# relayBoard.net
KiCad netlist of a schematic drawn in EAGLE
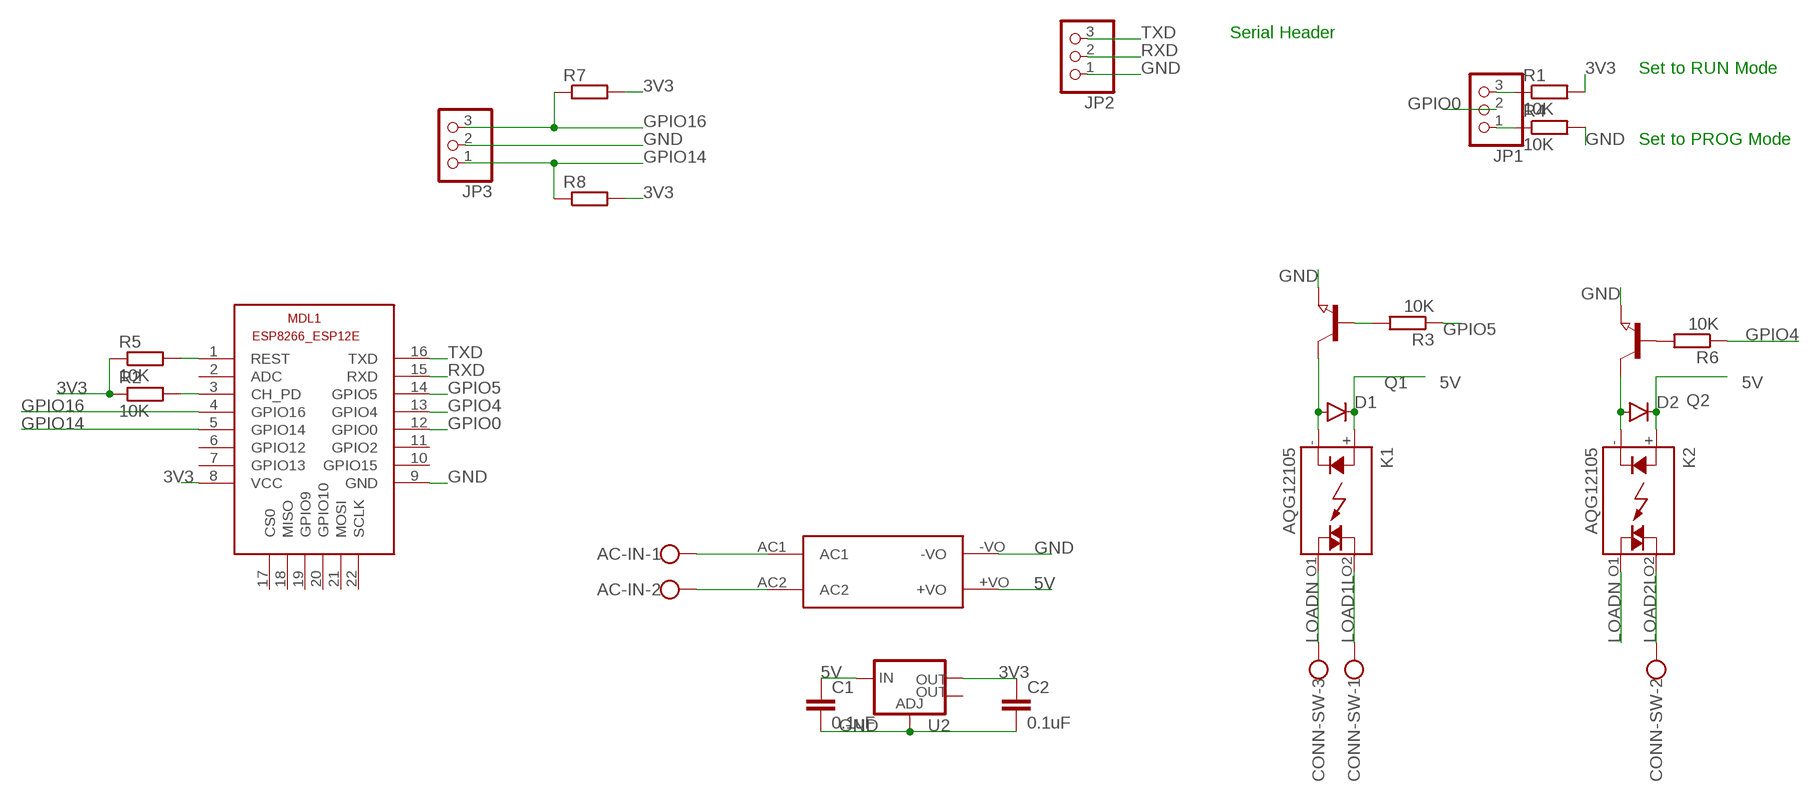
[diagram p0: schematic, sheet 1]

(export (version "E")
  (design (tool "Eeschema 10.0.6"))
  (components
    (comp (ref "AC-IN")
      (value "W237-102")
      (footprint "eagle-import:W237-102")
      (fields (field (name "MPN") "237-102"))
      (libsource (lib "eagle-import") (part "W237-102"))
    )
    (comp (ref "C1")
      (value "0.1uF")
      (footprint "eagle-import:0603-CAP")
      (libsource (lib "eagle-import") (part "0.1UF-25V-5%(0603)"))
    )
    (comp (ref "C2")
      (value "0.1uF")
      (footprint "eagle-import:0603-CAP")
      (libsource (lib "eagle-import") (part "0.1UF-25V-5%(0603)"))
    )
    (comp (ref "CONN-SW")
      (value "W237-103")
      (footprint "eagle-import:W237-103")
      (fields (field (name "MPN") "237-103"))
      (libsource (lib "eagle-import") (part "W237-103"))
    )
    (comp (ref "D1")
      (value "DIODESMA")
      (footprint "eagle-import:SMA-DIODE")
      (libsource (lib "eagle-import") (part "DIODESMA"))
    )
    (comp (ref "D2")
      (value "DIODESMA")
      (footprint "eagle-import:SMA-DIODE")
      (libsource (lib "eagle-import") (part "DIODESMA"))
    )
    (comp (ref "JP1")
      (value "PINHD-1X3")
      (footprint "eagle-import:1X03")
      (libsource (lib "eagle-import") (part "PINHD-1X3"))
    )
    (comp (ref "JP2")
      (value "PINHD-1X3")
      (footprint "eagle-import:1X03")
      (libsource (lib "eagle-import") (part "PINHD-1X3"))
    )
    (comp (ref "JP3")
      (value "PINHD-1X3")
      (footprint "eagle-import:1X03")
      (libsource (lib "eagle-import") (part "PINHD-1X3"))
    )
    (comp (ref "K1")
      (value "AQG12105")
      (footprint "eagle-import:AQG")
      (fields (field (name "MF") "AROMAT/ MATSUSHITA"))
      (libsource (lib "eagle-import") (part "AQG12105"))
    )
    (comp (ref "K2")
      (value "AQG12105")
      (footprint "eagle-import:AQG")
      (fields (field (name "MF") "AROMAT/ MATSUSHITA"))
      (libsource (lib "eagle-import") (part "AQG12105"))
    )
    (comp (ref "MDL1")
      (value "ESP8266-12EESP8266-ESP12E")
      (footprint "eagle-import:ESP8266-ESP12E")
      (libsource (lib "eagle-import") (part "ESP8266-12EESP8266-ESP12E"))
    )
    (comp (ref "Q1")
      (value "NPN-TRANSISTOR_SOT23")
      (footprint "eagle-import:SOT23")
      (libsource (lib "eagle-import") (part "NPN-TRANSISTOR_SOT23"))
    )
    (comp (ref "Q2")
      (value "NPN-TRANSISTOR_SOT23")
      (footprint "eagle-import:SOT23")
      (libsource (lib "eagle-import") (part "NPN-TRANSISTOR_SOT23"))
    )
    (comp (ref "R1")
      (value "10K")
      (footprint "eagle-import:R0805")
      (libsource (lib "eagle-import") (part "R-EU_R0805"))
    )
    (comp (ref "R2")
      (value "10K")
      (footprint "eagle-import:R0805")
      (libsource (lib "eagle-import") (part "R-EU_R0805"))
    )
    (comp (ref "R3")
      (value "10K")
      (footprint "eagle-import:R0805")
      (libsource (lib "eagle-import") (part "R-EU_R0805"))
    )
    (comp (ref "R4")
      (value "10K")
      (footprint "eagle-import:R0805")
      (libsource (lib "eagle-import") (part "R-EU_R0805"))
    )
    (comp (ref "R5")
      (value "10K")
      (footprint "eagle-import:R0805")
      (libsource (lib "eagle-import") (part "R-EU_R0805"))
    )
    (comp (ref "R6")
      (value "10K")
      (footprint "eagle-import:R0805")
      (libsource (lib "eagle-import") (part "R-EU_R0805"))
    )
    (comp (ref "R7")
      (value "R-EU_R0805")
      (footprint "eagle-import:R0805")
      (libsource (lib "eagle-import") (part "R-EU_R0805"))
    )
    (comp (ref "R8")
      (value "R-EU_R0805")
      (footprint "eagle-import:R0805")
      (libsource (lib "eagle-import") (part "R-EU_R0805"))
    )
    (comp (ref "U$4")
      (value "HLK-PM01")
      (footprint "eagle-import:HLK-PM01")
      (libsource (lib "eagle-import") (part "HLK-PM01"))
    )
    (comp (ref "U2")
      (value "V_REG_LM1117SOT223")
      (footprint "eagle-import:SOT223")
      (libsource (lib "eagle-import") (part "V_REG_LM1117SOT223"))
    )
  )
  (nets
    (net (code "1") (name "/3V3") (class "Default")
      (node (ref "C2") (pin "1") (pinfunction "1_1") (pintype "passive"))
      (node (ref "MDL1") (pin "8") (pinfunction "VCC_8") (pintype "bidirectional"))
      (node (ref "R1") (pin "2") (pinfunction "2_2") (pintype "passive"))
      (node (ref "R2") (pin "1") (pinfunction "1_1") (pintype "passive"))
      (node (ref "R5") (pin "1") (pinfunction "1_1") (pintype "passive"))
      (node (ref "R7") (pin "2") (pinfunction "2_2") (pintype "passive"))
      (node (ref "R8") (pin "2") (pinfunction "2_2") (pintype "passive"))
      (node (ref "U2") (pin "2") (pinfunction "OUT_2") (pintype "output"))
    )
    (net (code "2") (name "/5V") (class "Default")
      (node (ref "C1") (pin "1") (pinfunction "1_1") (pintype "passive"))
      (node (ref "D1") (pin "C") (pinfunction "C_C") (pintype "passive"))
      (node (ref "D2") (pin "C") (pinfunction "C_C") (pintype "passive"))
      (node (ref "K1") (pin "+") (pinfunction "A_+") (pintype "passive"))
      (node (ref "K2") (pin "+") (pinfunction "A_+") (pintype "passive"))
      (node (ref "U$4") (pin "+VO") (pinfunction "+VO_+VO") (pintype "bidirectional"))
      (node (ref "U2") (pin "3") (pinfunction "IN_3") (pintype "input"))
    )
    (net (code "3") (name "/GND") (class "Default")
      (node (ref "C1") (pin "2") (pinfunction "2_2") (pintype "passive"))
      (node (ref "C2") (pin "2") (pinfunction "2_2") (pintype "passive"))
      (node (ref "JP2") (pin "1") (pinfunction "1_1") (pintype "passive"))
      (node (ref "JP3") (pin "2") (pinfunction "2_2") (pintype "passive"))
      (node (ref "MDL1") (pin "9") (pinfunction "GND_9") (pintype "bidirectional"))
      (node (ref "Q1") (pin "2") (pinfunction "E_2") (pintype "passive"))
      (node (ref "Q2") (pin "2") (pinfunction "E_2") (pintype "passive"))
      (node (ref "R4") (pin "2") (pinfunction "2_2") (pintype "passive"))
      (node (ref "U$4") (pin "-VO") (pinfunction "-VO_-VO") (pintype "bidirectional"))
      (node (ref "U2") (pin "1") (pinfunction "ADJ_1") (pintype "input"))
    )
    (net (code "4") (name "/GPIO0") (class "Default")
      (node (ref "JP1") (pin "2") (pinfunction "2_2") (pintype "passive"))
      (node (ref "MDL1") (pin "12") (pinfunction "GPIO0_12") (pintype "bidirectional"))
    )
    (net (code "5") (name "/GPIO4") (class "Default")
      (node (ref "MDL1") (pin "13") (pinfunction "GPIO4_13") (pintype "bidirectional"))
      (node (ref "R6") (pin "1") (pinfunction "1_1") (pintype "passive"))
    )
    (net (code "6") (name "/GPIO5") (class "Default")
      (node (ref "MDL1") (pin "14") (pinfunction "GPIO5_14") (pintype "bidirectional"))
      (node (ref "R3") (pin "1") (pinfunction "1_1") (pintype "passive"))
    )
    (net (code "7") (name "/GPIO14") (class "Default")
      (node (ref "JP3") (pin "1") (pinfunction "1_1") (pintype "passive"))
      (node (ref "MDL1") (pin "5") (pinfunction "GPIO14_5") (pintype "bidirectional"))
      (node (ref "R8") (pin "1") (pinfunction "1_1") (pintype "passive"))
    )
    (net (code "8") (name "/GPIO16") (class "Default")
      (node (ref "JP3") (pin "3") (pinfunction "3_3") (pintype "passive"))
      (node (ref "MDL1") (pin "4") (pinfunction "GPIO16_4") (pintype "bidirectional"))
      (node (ref "R7") (pin "1") (pinfunction "1_1") (pintype "passive"))
    )
    (net (code "9") (name "/LOAD1L") (class "Default")
      (node (ref "CONN-SW") (pin "1") (pinfunction "KL_1") (pintype "passive"))
      (node (ref "K1") (pin "O2") (pinfunction "DS1_O2") (pintype "passive"))
    )
    (net (code "10") (name "/LOAD2L") (class "Default")
      (node (ref "CONN-SW") (pin "2") (pinfunction "KL_2") (pintype "passive"))
      (node (ref "K2") (pin "O2") (pinfunction "DS1_O2") (pintype "passive"))
    )
    (net (code "11") (name "/LOADN") (class "Default")
      (node (ref "CONN-SW") (pin "3") (pinfunction "KL_3") (pintype "passive"))
      (node (ref "K1") (pin "O1") (pinfunction "DS2_O1") (pintype "passive"))
      (node (ref "K2") (pin "O1") (pinfunction "DS2_O1") (pintype "passive"))
    )
    (net (code "12") (name "/RXD") (class "Default")
      (node (ref "JP2") (pin "2") (pinfunction "2_2") (pintype "passive"))
      (node (ref "MDL1") (pin "15") (pinfunction "RXD_15") (pintype "bidirectional"))
    )
    (net (code "13") (name "/TXD") (class "Default")
      (node (ref "JP2") (pin "3") (pinfunction "3_3") (pintype "passive"))
      (node (ref "MDL1") (pin "16") (pinfunction "TXD_16") (pintype "bidirectional"))
    )
    (net (code "14") (name "Net-(AC-INA-KL)") (class "Default")
      (node (ref "AC-IN") (pin "1") (pinfunction "KL_1") (pintype "passive"))
      (node (ref "U$4") (pin "AC1") (pinfunction "AC1_AC1") (pintype "bidirectional"))
    )
    (net (code "15") (name "Net-(AC-INB-KL)") (class "Default")
      (node (ref "AC-IN") (pin "2") (pinfunction "KL_2") (pintype "passive"))
      (node (ref "U$4") (pin "AC2") (pinfunction "AC2_AC2") (pintype "bidirectional"))
    )
    (net (code "16") (name "Net-(JP1-Pad1)") (class "Default")
      (node (ref "JP1") (pin "1") (pinfunction "1_1") (pintype "passive"))
      (node (ref "R4") (pin "1") (pinfunction "1_1") (pintype "passive"))
    )
    (net (code "17") (name "Net-(JP1-Pad3)") (class "Default")
      (node (ref "JP1") (pin "3") (pinfunction "3_3") (pintype "passive"))
      (node (ref "R1") (pin "1") (pinfunction "1_1") (pintype "passive"))
    )
    (net (code "18") (name "Net-(K1-K)") (class "Default")
      (node (ref "D1") (pin "A") (pinfunction "A_A") (pintype "passive"))
      (node (ref "K1") (pin "-") (pinfunction "K_-") (pintype "passive"))
      (node (ref "Q1") (pin "3") (pinfunction "C_3") (pintype "passive"))
    )
    (net (code "19") (name "Net-(K2-K)") (class "Default")
      (node (ref "D2") (pin "A") (pinfunction "A_A") (pintype "passive"))
      (node (ref "K2") (pin "-") (pinfunction "K_-") (pintype "passive"))
      (node (ref "Q2") (pin "3") (pinfunction "C_3") (pintype "passive"))
    )
    (net (code "20") (name "Net-(MDL1-CH_PD)") (class "Default")
      (node (ref "MDL1") (pin "3") (pinfunction "CH_PD_3") (pintype "bidirectional"))
      (node (ref "R2") (pin "2") (pinfunction "2_2") (pintype "passive"))
    )
    (net (code "21") (name "Net-(MDL1-REST)") (class "Default")
      (node (ref "MDL1") (pin "1") (pinfunction "REST_1") (pintype "bidirectional"))
      (node (ref "R5") (pin "2") (pinfunction "2_2") (pintype "passive"))
    )
    (net (code "22") (name "Net-(Q1-B)") (class "Default")
      (node (ref "Q1") (pin "1") (pinfunction "B_1") (pintype "passive"))
      (node (ref "R3") (pin "2") (pinfunction "2_2") (pintype "passive"))
    )
    (net (code "23") (name "Net-(Q2-B)") (class "Default")
      (node (ref "Q2") (pin "1") (pinfunction "B_1") (pintype "passive"))
      (node (ref "R6") (pin "2") (pinfunction "2_2") (pintype "passive"))
    )
    (net (code "24") (name "unconnected-(MDL1-ADC-Pad2)") (class "Default")
      (node (ref "MDL1") (pin "2") (pinfunction "ADC_2") (pintype "bidirectional"))
    )
    (net (code "25") (name "unconnected-(MDL1-CS0-Pad17)") (class "Default")
      (node (ref "MDL1") (pin "17") (pinfunction "CS0_17") (pintype "bidirectional"))
    )
    (net (code "26") (name "unconnected-(MDL1-GPIO2-Pad11)") (class "Default")
      (node (ref "MDL1") (pin "11") (pinfunction "GPIO2_11") (pintype "bidirectional"))
    )
    (net (code "27") (name "unconnected-(MDL1-GPIO9-Pad19)") (class "Default")
      (node (ref "MDL1") (pin "19") (pinfunction "GPIO9_19") (pintype "bidirectional"))
    )
    (net (code "28") (name "unconnected-(MDL1-GPIO10-Pad20)") (class "Default")
      (node (ref "MDL1") (pin "20") (pinfunction "GPIO10_20") (pintype "bidirectional"))
    )
    (net (code "29") (name "unconnected-(MDL1-GPIO12-Pad6)") (class "Default")
      (node (ref "MDL1") (pin "6") (pinfunction "GPIO12_6") (pintype "bidirectional"))
    )
    (net (code "30") (name "unconnected-(MDL1-GPIO13-Pad7)") (class "Default")
      (node (ref "MDL1") (pin "7") (pinfunction "GPIO13_7") (pintype "bidirectional"))
    )
    (net (code "31") (name "unconnected-(MDL1-GPIO15-Pad10)") (class "Default")
      (node (ref "MDL1") (pin "10") (pinfunction "GPIO15_10") (pintype "bidirectional"))
    )
    (net (code "32") (name "unconnected-(MDL1-MISO-Pad18)") (class "Default")
      (node (ref "MDL1") (pin "18") (pinfunction "MISO_18") (pintype "bidirectional"))
    )
    (net (code "33") (name "unconnected-(MDL1-MOSI-Pad21)") (class "Default")
      (node (ref "MDL1") (pin "21") (pinfunction "MOSI_21") (pintype "bidirectional"))
    )
    (net (code "34") (name "unconnected-(MDL1-SCLK-Pad22)") (class "Default")
      (node (ref "MDL1") (pin "22") (pinfunction "SCLK_22") (pintype "bidirectional"))
    )
    (net (code "35") (name "unconnected-(U2-OUT-Pad4)") (class "Default")
      (node (ref "U2") (pin "4") (pinfunction "OUT_4") (pintype "output"))
    )
  )
)
